# pcb.net
KiCad netlist of a schematic drawn in EAGLE
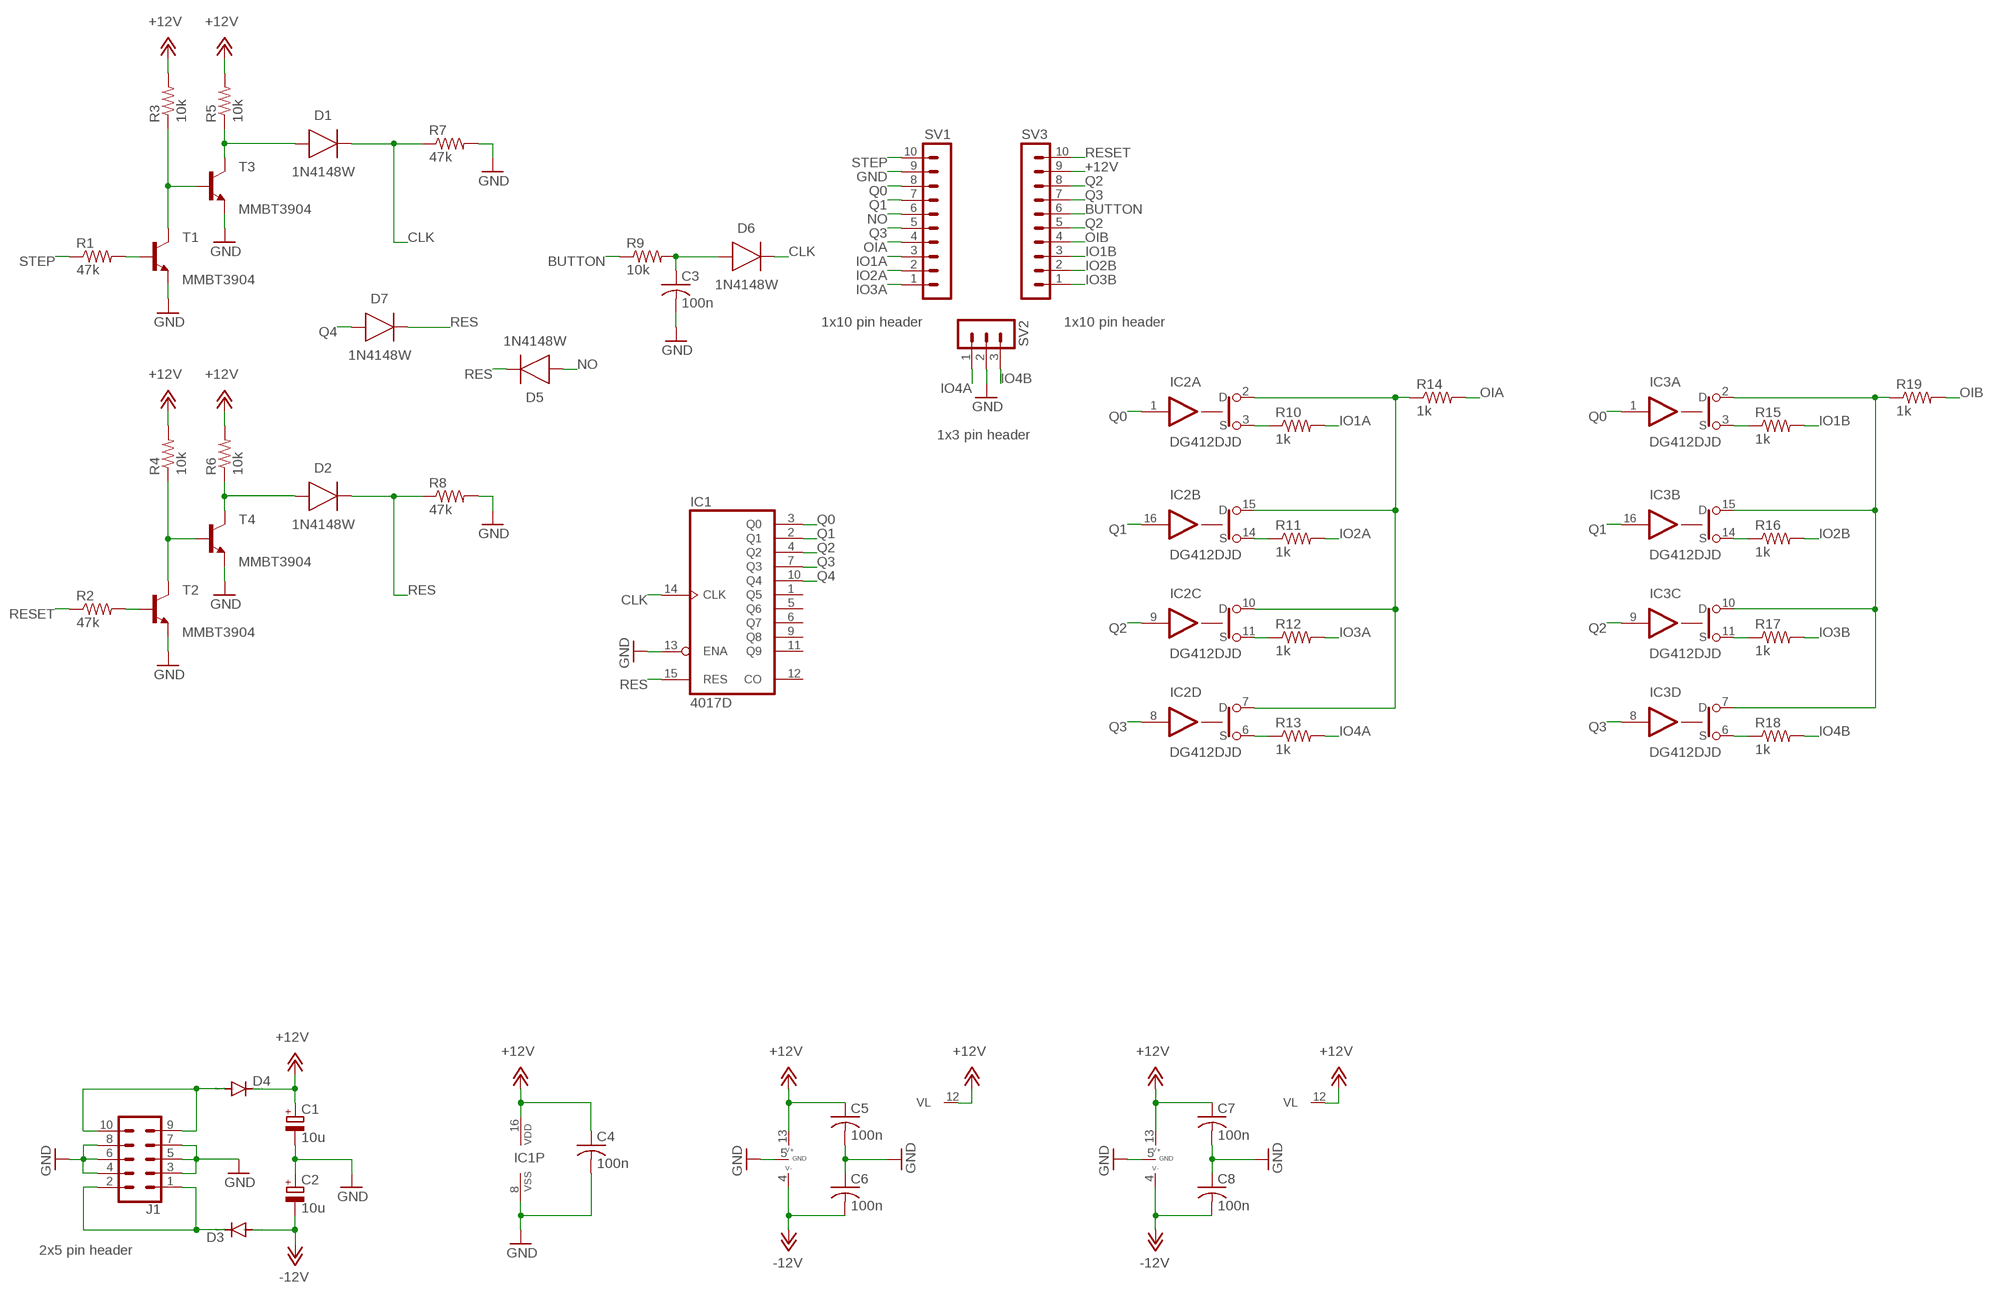
[diagram p0: schematic, sheet 1]

(export (version "E")
  (design (tool "Eeschema 10.0.6"))
  (components
    (comp (ref "C1")
      (value "10u")
      (footprint "eagle-import:153CLV-0605")
      (libsource (lib "eagle-import") (part "CPOL-EU153CLV-0605"))
    )
    (comp (ref "C2")
      (value "10u")
      (footprint "eagle-import:153CLV-0605")
      (libsource (lib "eagle-import") (part "CPOL-EU153CLV-0605"))
    )
    (comp (ref "C3")
      (value "100n")
      (footprint "eagle-import:C0603")
      (libsource (lib "eagle-import") (part "C-USC0603"))
    )
    (comp (ref "C4")
      (value "100n")
      (footprint "eagle-import:C0603")
      (libsource (lib "eagle-import") (part "C-USC0603"))
    )
    (comp (ref "C5")
      (value "100n")
      (footprint "eagle-import:C0603")
      (libsource (lib "eagle-import") (part "C-USC0603"))
    )
    (comp (ref "C6")
      (value "100n")
      (footprint "eagle-import:C0603")
      (libsource (lib "eagle-import") (part "C-USC0603"))
    )
    (comp (ref "C7")
      (value "100n")
      (footprint "eagle-import:C0603")
      (libsource (lib "eagle-import") (part "C-USC0603"))
    )
    (comp (ref "C8")
      (value "100n")
      (footprint "eagle-import:C0603")
      (libsource (lib "eagle-import") (part "C-USC0603"))
    )
    (comp (ref "D1")
      (value "1N4148W")
      (footprint "eagle-import:SOD3715X135")
      (fields (field (name "MANUFACTURER") "Diodes Incorporated"))
      (libsource (lib "eagle-import") (part "DIODE__SOD123G1N4148W-7-F"))
    )
    (comp (ref "D2")
      (value "1N4148W")
      (footprint "eagle-import:SOD3715X135")
      (fields (field (name "MANUFACTURER") "Diodes Incorporated"))
      (libsource (lib "eagle-import") (part "DIODE__SOD123G1N4148W-7-F"))
    )
    (comp (ref "D3")
      (value "DIODE-SOD123")
      (footprint "eagle-import:SOD123")
      (libsource (lib "eagle-import") (part "DIODE-SOD123"))
    )
    (comp (ref "D4")
      (value "DIODE-SOD123")
      (footprint "eagle-import:SOD123")
      (libsource (lib "eagle-import") (part "DIODE-SOD123"))
    )
    (comp (ref "D5")
      (value "1N4148W")
      (footprint "eagle-import:SOD3715X135")
      (fields (field (name "MANUFACTURER") "Diodes Incorporated"))
      (libsource (lib "eagle-import") (part "DIODE__SOD123G1N4148W-7-F"))
    )
    (comp (ref "D6")
      (value "1N4148W")
      (footprint "eagle-import:SOD3715X135")
      (fields (field (name "MANUFACTURER") "Diodes Incorporated"))
      (libsource (lib "eagle-import") (part "DIODE__SOD123G1N4148W-7-F"))
    )
    (comp (ref "D7")
      (value "1N4148W")
      (footprint "eagle-import:SOD3715X135")
      (fields (field (name "MANUFACTURER") "Diodes Incorporated"))
      (libsource (lib "eagle-import") (part "DIODE__SOD123G1N4148W-7-F"))
    )
    (comp (ref "IC1")
      (value "4017D")
      (footprint "eagle-import:SO16")
      (libsource (lib "eagle-import") (part "4017D"))
    )
    (comp (ref "IC2")
      (value "DG412DJD")
      (footprint "eagle-import:SO16")
      (libsource (lib "eagle-import") (part "DG412DJD"))
    )
    (comp (ref "IC3")
      (value "DG412DJD")
      (footprint "eagle-import:SO16")
      (libsource (lib "eagle-import") (part "DG412DJD"))
    )
    (comp (ref "J1")
      (value "2x5 pin header")
      (footprint "eagle-import:2X5-SHROUDED")
      (libsource (lib "eagle-import") (part "CONN_05X2SHD"))
    )
    (comp (ref "R1")
      (value "47k")
      (footprint "eagle-import:R0603")
      (libsource (lib "eagle-import") (part "R-US_R0603"))
    )
    (comp (ref "R2")
      (value "47k")
      (footprint "eagle-import:R0603")
      (libsource (lib "eagle-import") (part "R-US_R0603"))
    )
    (comp (ref "R3")
      (value "10k")
      (footprint "eagle-import:R0603")
      (libsource (lib "eagle-import") (part "R-US_R0603"))
    )
    (comp (ref "R4")
      (value "10k")
      (footprint "eagle-import:R0603")
      (libsource (lib "eagle-import") (part "R-US_R0603"))
    )
    (comp (ref "R5")
      (value "10k")
      (footprint "eagle-import:R0603")
      (libsource (lib "eagle-import") (part "R-US_R0603"))
    )
    (comp (ref "R6")
      (value "10k")
      (footprint "eagle-import:R0603")
      (libsource (lib "eagle-import") (part "R-US_R0603"))
    )
    (comp (ref "R7")
      (value "47k")
      (footprint "eagle-import:R0603")
      (libsource (lib "eagle-import") (part "R-US_R0603"))
    )
    (comp (ref "R8")
      (value "47k")
      (footprint "eagle-import:R0603")
      (libsource (lib "eagle-import") (part "R-US_R0603"))
    )
    (comp (ref "R9")
      (value "10k")
      (footprint "eagle-import:R0603")
      (libsource (lib "eagle-import") (part "R-US_R0603"))
    )
    (comp (ref "R10")
      (value "1k")
      (footprint "eagle-import:R0603")
      (libsource (lib "eagle-import") (part "R-US_R0603"))
    )
    (comp (ref "R11")
      (value "1k")
      (footprint "eagle-import:R0603")
      (libsource (lib "eagle-import") (part "R-US_R0603"))
    )
    (comp (ref "R12")
      (value "1k")
      (footprint "eagle-import:R0603")
      (libsource (lib "eagle-import") (part "R-US_R0603"))
    )
    (comp (ref "R13")
      (value "1k")
      (footprint "eagle-import:R0603")
      (libsource (lib "eagle-import") (part "R-US_R0603"))
    )
    (comp (ref "R14")
      (value "1k")
      (footprint "eagle-import:R0603")
      (libsource (lib "eagle-import") (part "R-US_R0603"))
    )
    (comp (ref "R15")
      (value "1k")
      (footprint "eagle-import:R0603")
      (libsource (lib "eagle-import") (part "R-US_R0603"))
    )
    (comp (ref "R16")
      (value "1k")
      (footprint "eagle-import:R0603")
      (libsource (lib "eagle-import") (part "R-US_R0603"))
    )
    (comp (ref "R17")
      (value "1k")
      (footprint "eagle-import:R0603")
      (libsource (lib "eagle-import") (part "R-US_R0603"))
    )
    (comp (ref "R18")
      (value "1k")
      (footprint "eagle-import:R0603")
      (libsource (lib "eagle-import") (part "R-US_R0603"))
    )
    (comp (ref "R19")
      (value "1k")
      (footprint "eagle-import:R0603")
      (libsource (lib "eagle-import") (part "R-US_R0603"))
    )
    (comp (ref "SV1")
      (value "1x10 pin header")
      (footprint "eagle-import:MA10-1")
      (libsource (lib "eagle-import") (part "MA10-1"))
    )
    (comp (ref "SV2")
      (value "1x3 pin header")
      (footprint "eagle-import:MA03-1")
      (libsource (lib "eagle-import") (part "MA03-1"))
    )
    (comp (ref "SV3")
      (value "1x10 pin header")
      (footprint "eagle-import:MA10-1")
      (libsource (lib "eagle-import") (part "MA10-1"))
    )
    (comp (ref "T1")
      (value "MMBT3904")
      (footprint "eagle-import:SOT23-BEC")
      (libsource (lib "eagle-import") (part "-NPN-SOT23-BECMMBT3904LT1"))
    )
    (comp (ref "T2")
      (value "MMBT3904")
      (footprint "eagle-import:SOT23-BEC")
      (libsource (lib "eagle-import") (part "-NPN-SOT23-BECMMBT3904LT1"))
    )
    (comp (ref "T3")
      (value "MMBT3904")
      (footprint "eagle-import:SOT23-BEC")
      (libsource (lib "eagle-import") (part "-NPN-SOT23-BECMMBT3904LT1"))
    )
    (comp (ref "T4")
      (value "MMBT3904")
      (footprint "eagle-import:SOT23-BEC")
      (libsource (lib "eagle-import") (part "-NPN-SOT23-BECMMBT3904LT1"))
    )
  )
  (nets
    (net (code "1") (name "+12V") (class "Default")
      (node (ref "C1") (pin "+") (pinfunction "+_+") (pintype "passive"))
      (node (ref "C4") (pin "1") (pinfunction "1_1") (pintype "passive"))
      (node (ref "C5") (pin "1") (pinfunction "1_1") (pintype "passive"))
      (node (ref "C7") (pin "1") (pinfunction "1_1") (pintype "passive"))
      (node (ref "D4") (pin "C") (pinfunction "C_C") (pintype "passive"))
      (node (ref "IC1") (pin "16") (pinfunction "VDD_16") (pintype "power_in"))
      (node (ref "IC2") (pin "12") (pinfunction "VL_12") (pintype "input"))
      (node (ref "IC2") (pin "13") (pinfunction "V+_13") (pintype "power_in"))
      (node (ref "IC3") (pin "12") (pinfunction "VL_12") (pintype "input"))
      (node (ref "IC3") (pin "13") (pinfunction "V+_13") (pintype "power_in"))
      (node (ref "R3") (pin "2") (pinfunction "2_2") (pintype "passive"))
      (node (ref "R4") (pin "2") (pinfunction "2_2") (pintype "passive"))
      (node (ref "R5") (pin "2") (pinfunction "2_2") (pintype "passive"))
      (node (ref "R6") (pin "2") (pinfunction "2_2") (pintype "passive"))
      (node (ref "SV3") (pin "9") (pinfunction "9_9") (pintype "passive"))
    )
    (net (code "2") (name "-12V") (class "Default")
      (node (ref "C2") (pin "-") (pinfunction "-_-") (pintype "passive"))
      (node (ref "C6") (pin "2") (pinfunction "2_2") (pintype "passive"))
      (node (ref "C8") (pin "2") (pinfunction "2_2") (pintype "passive"))
      (node (ref "D3") (pin "A") (pinfunction "A_A") (pintype "passive"))
      (node (ref "IC2") (pin "4") (pinfunction "V-_4") (pintype "power_in"))
      (node (ref "IC3") (pin "4") (pinfunction "V-_4") (pintype "power_in"))
    )
    (net (code "3") (name "/BUTTON") (class "Default")
      (node (ref "R9") (pin "1") (pinfunction "1_1") (pintype "passive"))
      (node (ref "SV3") (pin "6") (pinfunction "6_6") (pintype "passive"))
    )
    (net (code "4") (name "/CLK") (class "Default")
      (node (ref "D1") (pin "1") (pinfunction "C_1") (pintype "passive"))
      (node (ref "D6") (pin "1") (pinfunction "C_1") (pintype "passive"))
      (node (ref "IC1") (pin "14") (pinfunction "CLK_14") (pintype "input"))
      (node (ref "R7") (pin "1") (pinfunction "1_1") (pintype "passive"))
    )
    (net (code "5") (name "/IO1A") (class "Default")
      (node (ref "R10") (pin "2") (pinfunction "2_2") (pintype "passive"))
      (node (ref "SV1") (pin "3") (pinfunction "3_3") (pintype "passive"))
    )
    (net (code "6") (name "/IO1B") (class "Default")
      (node (ref "R15") (pin "2") (pinfunction "2_2") (pintype "passive"))
      (node (ref "SV3") (pin "3") (pinfunction "3_3") (pintype "passive"))
    )
    (net (code "7") (name "/IO2A") (class "Default")
      (node (ref "R11") (pin "2") (pinfunction "2_2") (pintype "passive"))
      (node (ref "SV1") (pin "2") (pinfunction "2_2") (pintype "passive"))
    )
    (net (code "8") (name "/IO2B") (class "Default")
      (node (ref "R16") (pin "2") (pinfunction "2_2") (pintype "passive"))
      (node (ref "SV3") (pin "2") (pinfunction "2_2") (pintype "passive"))
    )
    (net (code "9") (name "/IO3A") (class "Default")
      (node (ref "R12") (pin "2") (pinfunction "2_2") (pintype "passive"))
      (node (ref "SV1") (pin "1") (pinfunction "1_1") (pintype "passive"))
    )
    (net (code "10") (name "/IO3B") (class "Default")
      (node (ref "R17") (pin "2") (pinfunction "2_2") (pintype "passive"))
      (node (ref "SV3") (pin "1") (pinfunction "1_1") (pintype "passive"))
    )
    (net (code "11") (name "/IO4A") (class "Default")
      (node (ref "R13") (pin "2") (pinfunction "2_2") (pintype "passive"))
      (node (ref "SV2") (pin "1") (pinfunction "1_1") (pintype "passive"))
    )
    (net (code "12") (name "/IO4B") (class "Default")
      (node (ref "R18") (pin "2") (pinfunction "2_2") (pintype "passive"))
      (node (ref "SV2") (pin "3") (pinfunction "3_3") (pintype "passive"))
    )
    (net (code "13") (name "/NO") (class "Default")
      (node (ref "D5") (pin "2") (pinfunction "A_2") (pintype "passive"))
      (node (ref "SV1") (pin "6") (pinfunction "6_6") (pintype "passive"))
    )
    (net (code "14") (name "/OIA") (class "Default")
      (node (ref "R14") (pin "2") (pinfunction "2_2") (pintype "passive"))
      (node (ref "SV1") (pin "4") (pinfunction "4_4") (pintype "passive"))
    )
    (net (code "15") (name "/OIB") (class "Default")
      (node (ref "R19") (pin "2") (pinfunction "2_2") (pintype "passive"))
      (node (ref "SV3") (pin "4") (pinfunction "4_4") (pintype "passive"))
    )
    (net (code "16") (name "/Q0") (class "Default")
      (node (ref "IC1") (pin "3") (pinfunction "Q0_3") (pintype "output"))
      (node (ref "IC2") (pin "1") (pinfunction "IN_1") (pintype "input"))
      (node (ref "IC3") (pin "1") (pinfunction "IN_1") (pintype "input"))
      (node (ref "SV1") (pin "8") (pinfunction "8_8") (pintype "passive"))
    )
    (net (code "17") (name "/Q1") (class "Default")
      (node (ref "IC1") (pin "2") (pinfunction "Q1_2") (pintype "output"))
      (node (ref "IC2") (pin "16") (pinfunction "IN_16") (pintype "input"))
      (node (ref "IC3") (pin "16") (pinfunction "IN_16") (pintype "input"))
      (node (ref "SV1") (pin "7") (pinfunction "7_7") (pintype "passive"))
    )
    (net (code "18") (name "/Q2") (class "Default")
      (node (ref "IC1") (pin "4") (pinfunction "Q2_4") (pintype "output"))
      (node (ref "IC2") (pin "9") (pinfunction "IN_9") (pintype "input"))
      (node (ref "IC3") (pin "9") (pinfunction "IN_9") (pintype "input"))
      (node (ref "SV3") (pin "5") (pinfunction "5_5") (pintype "passive"))
      (node (ref "SV3") (pin "8") (pinfunction "8_8") (pintype "passive"))
    )
    (net (code "19") (name "/Q3") (class "Default")
      (node (ref "IC1") (pin "7") (pinfunction "Q3_7") (pintype "output"))
      (node (ref "IC2") (pin "8") (pinfunction "IN_8") (pintype "input"))
      (node (ref "IC3") (pin "8") (pinfunction "IN_8") (pintype "input"))
      (node (ref "SV1") (pin "5") (pinfunction "5_5") (pintype "passive"))
      (node (ref "SV3") (pin "7") (pinfunction "7_7") (pintype "passive"))
    )
    (net (code "20") (name "/Q4") (class "Default")
      (node (ref "D7") (pin "2") (pinfunction "A_2") (pintype "passive"))
      (node (ref "IC1") (pin "10") (pinfunction "Q4_10") (pintype "output"))
    )
    (net (code "21") (name "/RES") (class "Default")
      (node (ref "D2") (pin "1") (pinfunction "C_1") (pintype "passive"))
      (node (ref "D5") (pin "1") (pinfunction "C_1") (pintype "passive"))
      (node (ref "D7") (pin "1") (pinfunction "C_1") (pintype "passive"))
      (node (ref "IC1") (pin "15") (pinfunction "RES_15") (pintype "input"))
      (node (ref "R8") (pin "1") (pinfunction "1_1") (pintype "passive"))
    )
    (net (code "22") (name "/RESET") (class "Default")
      (node (ref "R2") (pin "1") (pinfunction "1_1") (pintype "passive"))
      (node (ref "SV3") (pin "10") (pinfunction "10_10") (pintype "passive"))
    )
    (net (code "23") (name "/STEP") (class "Default")
      (node (ref "R1") (pin "1") (pinfunction "1_1") (pintype "passive"))
      (node (ref "SV1") (pin "10") (pinfunction "10_10") (pintype "passive"))
    )
    (net (code "24") (name "GND") (class "Default")
      (node (ref "C1") (pin "-") (pinfunction "-_-") (pintype "passive"))
      (node (ref "C2") (pin "+") (pinfunction "+_+") (pintype "passive"))
      (node (ref "C3") (pin "2") (pinfunction "2_2") (pintype "passive"))
      (node (ref "C4") (pin "2") (pinfunction "2_2") (pintype "passive"))
      (node (ref "C5") (pin "2") (pinfunction "2_2") (pintype "passive"))
      (node (ref "C6") (pin "1") (pinfunction "1_1") (pintype "passive"))
      (node (ref "C7") (pin "2") (pinfunction "2_2") (pintype "passive"))
      (node (ref "C8") (pin "1") (pinfunction "1_1") (pintype "passive"))
      (node (ref "IC1") (pin "13") (pinfunction "ENA_13") (pintype "input"))
      (node (ref "IC1") (pin "8") (pinfunction "VSS_8") (pintype "power_in"))
      (node (ref "IC2") (pin "5") (pinfunction "GND_5") (pintype "power_in"))
      (node (ref "IC3") (pin "5") (pinfunction "GND_5") (pintype "power_in"))
      (node (ref "J1") (pin "3") (pinfunction "3_3") (pintype "passive"))
      (node (ref "J1") (pin "4") (pinfunction "4_4") (pintype "passive"))
      (node (ref "J1") (pin "5") (pinfunction "5_5") (pintype "passive"))
      (node (ref "J1") (pin "6") (pinfunction "6_6") (pintype "passive"))
      (node (ref "J1") (pin "7") (pinfunction "7_7") (pintype "passive"))
      (node (ref "J1") (pin "8") (pinfunction "8_8") (pintype "passive"))
      (node (ref "R7") (pin "2") (pinfunction "2_2") (pintype "passive"))
      (node (ref "R8") (pin "2") (pinfunction "2_2") (pintype "passive"))
      (node (ref "SV1") (pin "9") (pinfunction "9_9") (pintype "passive"))
      (node (ref "SV2") (pin "2") (pinfunction "2_2") (pintype "passive"))
      (node (ref "T1") (pin "E") (pinfunction "E_E") (pintype "passive"))
      (node (ref "T2") (pin "E") (pinfunction "E_E") (pintype "passive"))
      (node (ref "T3") (pin "E") (pinfunction "E_E") (pintype "passive"))
      (node (ref "T4") (pin "E") (pinfunction "E_E") (pintype "passive"))
    )
    (net (code "25") (name "Net-(D1-A)") (class "Default")
      (node (ref "D1") (pin "2") (pinfunction "A_2") (pintype "passive"))
      (node (ref "R5") (pin "1") (pinfunction "1_1") (pintype "passive"))
      (node (ref "T3") (pin "C") (pinfunction "C_C") (pintype "passive"))
    )
    (net (code "26") (name "Net-(D2-A)") (class "Default")
      (node (ref "D2") (pin "2") (pinfunction "A_2") (pintype "passive"))
      (node (ref "R6") (pin "1") (pinfunction "1_1") (pintype "passive"))
      (node (ref "T4") (pin "C") (pinfunction "C_C") (pintype "passive"))
    )
    (net (code "27") (name "Net-(D3-PadC)") (class "Default")
      (node (ref "D3") (pin "C") (pinfunction "C_C") (pintype "passive"))
      (node (ref "J1") (pin "1") (pinfunction "1_1") (pintype "passive"))
      (node (ref "J1") (pin "2") (pinfunction "2_2") (pintype "passive"))
    )
    (net (code "28") (name "Net-(D4-PadA)") (class "Default")
      (node (ref "D4") (pin "A") (pinfunction "A_A") (pintype "passive"))
      (node (ref "J1") (pin "10") (pinfunction "10_10") (pintype "passive"))
      (node (ref "J1") (pin "9") (pinfunction "9_9") (pintype "passive"))
    )
    (net (code "29") (name "Net-(D6-A)") (class "Default")
      (node (ref "C3") (pin "1") (pinfunction "1_1") (pintype "passive"))
      (node (ref "D6") (pin "2") (pinfunction "A_2") (pintype "passive"))
      (node (ref "R9") (pin "2") (pinfunction "2_2") (pintype "passive"))
    )
    (net (code "30") (name "Net-(IC2A-D)") (class "Default")
      (node (ref "IC2") (pin "10") (pinfunction "D_10") (pintype "bidirectional"))
      (node (ref "IC2") (pin "15") (pinfunction "D_15") (pintype "bidirectional"))
      (node (ref "IC2") (pin "2") (pinfunction "D_2") (pintype "bidirectional"))
      (node (ref "IC2") (pin "7") (pinfunction "D_7") (pintype "bidirectional"))
      (node (ref "R14") (pin "1") (pinfunction "1_1") (pintype "passive"))
    )
    (net (code "31") (name "Net-(IC2A-S)") (class "Default")
      (node (ref "IC2") (pin "3") (pinfunction "S_3") (pintype "bidirectional"))
      (node (ref "R10") (pin "1") (pinfunction "1_1") (pintype "passive"))
    )
    (net (code "32") (name "Net-(IC2B-S)") (class "Default")
      (node (ref "IC2") (pin "14") (pinfunction "S_14") (pintype "bidirectional"))
      (node (ref "R11") (pin "1") (pinfunction "1_1") (pintype "passive"))
    )
    (net (code "33") (name "Net-(IC2C-S)") (class "Default")
      (node (ref "IC2") (pin "11") (pinfunction "S_11") (pintype "bidirectional"))
      (node (ref "R12") (pin "1") (pinfunction "1_1") (pintype "passive"))
    )
    (net (code "34") (name "Net-(IC2D-S)") (class "Default")
      (node (ref "IC2") (pin "6") (pinfunction "S_6") (pintype "bidirectional"))
      (node (ref "R13") (pin "1") (pinfunction "1_1") (pintype "passive"))
    )
    (net (code "35") (name "Net-(IC3A-D)") (class "Default")
      (node (ref "IC3") (pin "10") (pinfunction "D_10") (pintype "bidirectional"))
      (node (ref "IC3") (pin "15") (pinfunction "D_15") (pintype "bidirectional"))
      (node (ref "IC3") (pin "2") (pinfunction "D_2") (pintype "bidirectional"))
      (node (ref "IC3") (pin "7") (pinfunction "D_7") (pintype "bidirectional"))
      (node (ref "R19") (pin "1") (pinfunction "1_1") (pintype "passive"))
    )
    (net (code "36") (name "Net-(IC3A-S)") (class "Default")
      (node (ref "IC3") (pin "3") (pinfunction "S_3") (pintype "bidirectional"))
      (node (ref "R15") (pin "1") (pinfunction "1_1") (pintype "passive"))
    )
    (net (code "37") (name "Net-(IC3B-S)") (class "Default")
      (node (ref "IC3") (pin "14") (pinfunction "S_14") (pintype "bidirectional"))
      (node (ref "R16") (pin "1") (pinfunction "1_1") (pintype "passive"))
    )
    (net (code "38") (name "Net-(IC3C-S)") (class "Default")
      (node (ref "IC3") (pin "11") (pinfunction "S_11") (pintype "bidirectional"))
      (node (ref "R17") (pin "1") (pinfunction "1_1") (pintype "passive"))
    )
    (net (code "39") (name "Net-(IC3D-S)") (class "Default")
      (node (ref "IC3") (pin "6") (pinfunction "S_6") (pintype "bidirectional"))
      (node (ref "R18") (pin "1") (pinfunction "1_1") (pintype "passive"))
    )
    (net (code "40") (name "Net-(R1-Pad2)") (class "Default")
      (node (ref "R1") (pin "2") (pinfunction "2_2") (pintype "passive"))
      (node (ref "T1") (pin "B") (pinfunction "B_B") (pintype "passive"))
    )
    (net (code "41") (name "Net-(R2-Pad2)") (class "Default")
      (node (ref "R2") (pin "2") (pinfunction "2_2") (pintype "passive"))
      (node (ref "T2") (pin "B") (pinfunction "B_B") (pintype "passive"))
    )
    (net (code "42") (name "Net-(R3-Pad1)") (class "Default")
      (node (ref "R3") (pin "1") (pinfunction "1_1") (pintype "passive"))
      (node (ref "T1") (pin "C") (pinfunction "C_C") (pintype "passive"))
      (node (ref "T3") (pin "B") (pinfunction "B_B") (pintype "passive"))
    )
    (net (code "43") (name "Net-(R4-Pad1)") (class "Default")
      (node (ref "R4") (pin "1") (pinfunction "1_1") (pintype "passive"))
      (node (ref "T2") (pin "C") (pinfunction "C_C") (pintype "passive"))
      (node (ref "T4") (pin "B") (pinfunction "B_B") (pintype "passive"))
    )
    (net (code "44") (name "unconnected-(IC1A-CO-Pad12)") (class "Default")
      (node (ref "IC1") (pin "12") (pinfunction "CO_12") (pintype "output"))
    )
    (net (code "45") (name "unconnected-(IC1A-Q5-Pad1)") (class "Default")
      (node (ref "IC1") (pin "1") (pinfunction "Q5_1") (pintype "output"))
    )
    (net (code "46") (name "unconnected-(IC1A-Q6-Pad5)") (class "Default")
      (node (ref "IC1") (pin "5") (pinfunction "Q6_5") (pintype "output"))
    )
    (net (code "47") (name "unconnected-(IC1A-Q7-Pad6)") (class "Default")
      (node (ref "IC1") (pin "6") (pinfunction "Q7_6") (pintype "output"))
    )
    (net (code "48") (name "unconnected-(IC1A-Q8-Pad9)") (class "Default")
      (node (ref "IC1") (pin "9") (pinfunction "Q8_9") (pintype "output"))
    )
    (net (code "49") (name "unconnected-(IC1A-Q9-Pad11)") (class "Default")
      (node (ref "IC1") (pin "11") (pinfunction "Q9_11") (pintype "output"))
    )
  )
)
